# Central_Unit_V2.net
KiCad netlist of a schematic drawn in EAGLE
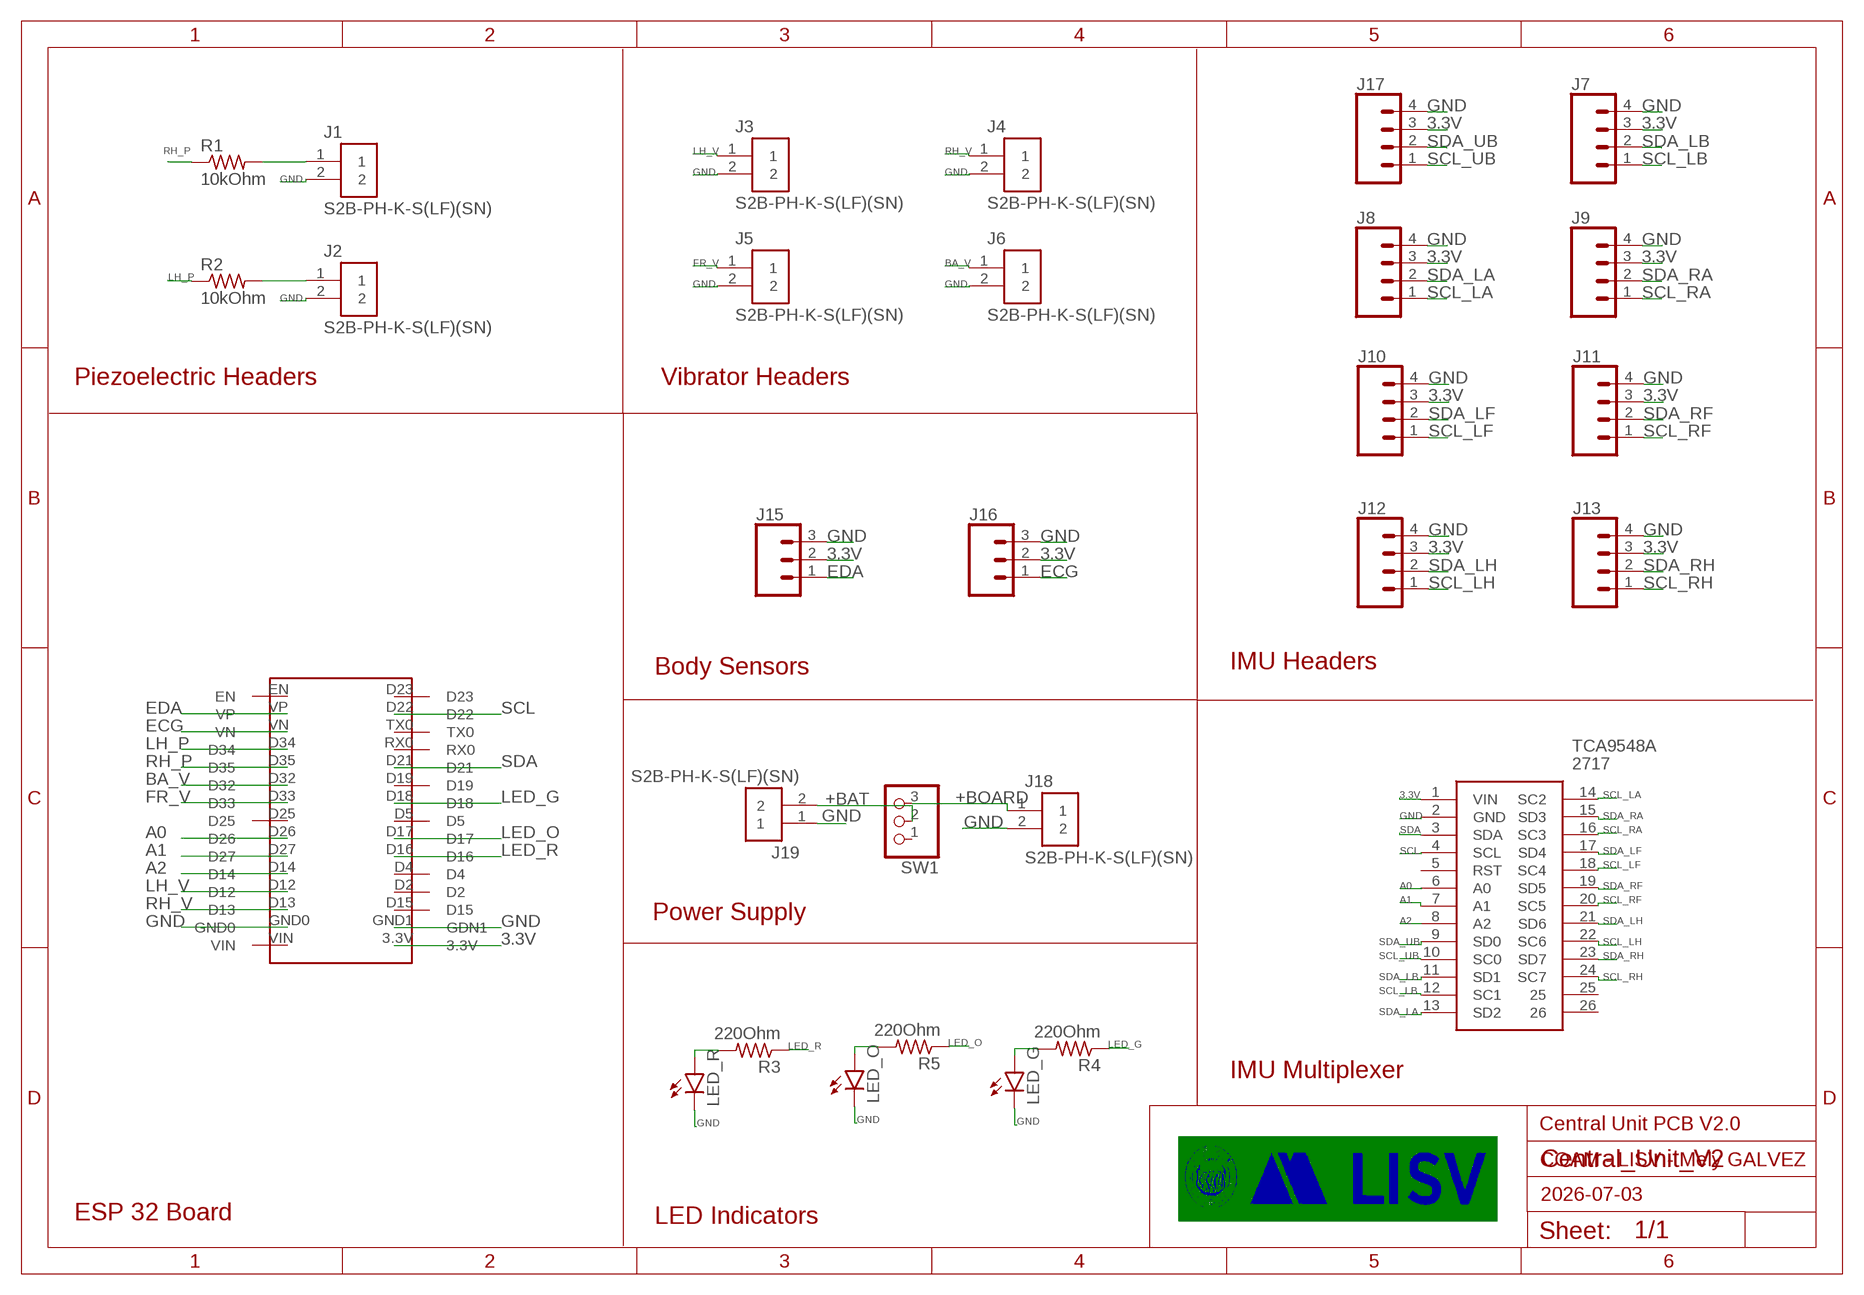
[diagram p0: schematic, sheet 1]

(export (version "E")
  (design (tool "Eeschema 10.0.6"))
  (components
    (comp (ref "J1")
      (value "S2B-PH-K-S(LF)(SN)")
      (footprint "eagle-import:S2B-PH-K-S(LF)(SN)")
      (fields
        (field (name "DIGI_KEY_PART_NUMBER") "455-1719-ND")
        (field (name "MANUFACTURER") "JST Sales America Inc.")
        (field (name "CREATED_BY") "PCBLayout.com")
      )
      (libsource (lib "eagle-import") (part "S2B-PH-K-S(LF)(SN)"))
    )
    (comp (ref "J2")
      (value "S2B-PH-K-S(LF)(SN)")
      (footprint "eagle-import:S2B-PH-K-S(LF)(SN)")
      (fields
        (field (name "DIGI_KEY_PART_NUMBER") "455-1719-ND")
        (field (name "MANUFACTURER") "JST Sales America Inc.")
        (field (name "CREATED_BY") "PCBLayout.com")
      )
      (libsource (lib "eagle-import") (part "S2B-PH-K-S(LF)(SN)"))
    )
    (comp (ref "J3")
      (value "S2B-PH-K-S(LF)(SN)")
      (footprint "eagle-import:S2B-PH-K-S(LF)(SN)")
      (fields
        (field (name "DIGI_KEY_PART_NUMBER") "455-1719-ND")
        (field (name "MANUFACTURER") "JST Sales America Inc.")
        (field (name "CREATED_BY") "PCBLayout.com")
      )
      (libsource (lib "eagle-import") (part "S2B-PH-K-S(LF)(SN)"))
    )
    (comp (ref "J4")
      (value "S2B-PH-K-S(LF)(SN)")
      (footprint "eagle-import:S2B-PH-K-S(LF)(SN)")
      (fields
        (field (name "DIGI_KEY_PART_NUMBER") "455-1719-ND")
        (field (name "MANUFACTURER") "JST Sales America Inc.")
        (field (name "CREATED_BY") "PCBLayout.com")
      )
      (libsource (lib "eagle-import") (part "S2B-PH-K-S(LF)(SN)"))
    )
    (comp (ref "J5")
      (value "S2B-PH-K-S(LF)(SN)")
      (footprint "eagle-import:S2B-PH-K-S(LF)(SN)")
      (fields
        (field (name "DIGI_KEY_PART_NUMBER") "455-1719-ND")
        (field (name "MANUFACTURER") "JST Sales America Inc.")
        (field (name "CREATED_BY") "PCBLayout.com")
      )
      (libsource (lib "eagle-import") (part "S2B-PH-K-S(LF)(SN)"))
    )
    (comp (ref "J6")
      (value "S2B-PH-K-S(LF)(SN)")
      (footprint "eagle-import:S2B-PH-K-S(LF)(SN)")
      (fields
        (field (name "DIGI_KEY_PART_NUMBER") "455-1719-ND")
        (field (name "MANUFACTURER") "JST Sales America Inc.")
        (field (name "CREATED_BY") "PCBLayout.com")
      )
      (libsource (lib "eagle-import") (part "S2B-PH-K-S(LF)(SN)"))
    )
    (comp (ref "J7")
      (value "CONN_04JST-PTH")
      (footprint "eagle-import:JST-4-PTH")
      (libsource (lib "eagle-import") (part "CONN_04JST-PTH"))
    )
    (comp (ref "J8")
      (value "CONN_04JST-PTH")
      (footprint "eagle-import:JST-4-PTH")
      (libsource (lib "eagle-import") (part "CONN_04JST-PTH"))
    )
    (comp (ref "J9")
      (value "CONN_04JST-PTH")
      (footprint "eagle-import:JST-4-PTH")
      (libsource (lib "eagle-import") (part "CONN_04JST-PTH"))
    )
    (comp (ref "J10")
      (value "CONN_04JST-PTH")
      (footprint "eagle-import:JST-4-PTH")
      (libsource (lib "eagle-import") (part "CONN_04JST-PTH"))
    )
    (comp (ref "J11")
      (value "CONN_04JST-PTH")
      (footprint "eagle-import:JST-4-PTH")
      (libsource (lib "eagle-import") (part "CONN_04JST-PTH"))
    )
    (comp (ref "J12")
      (value "CONN_04JST-PTH")
      (footprint "eagle-import:JST-4-PTH")
      (libsource (lib "eagle-import") (part "CONN_04JST-PTH"))
    )
    (comp (ref "J13")
      (value "CONN_04JST-PTH")
      (footprint "eagle-import:JST-4-PTH")
      (libsource (lib "eagle-import") (part "CONN_04JST-PTH"))
    )
    (comp (ref "J15")
      (value "CONN_03JST-PTH")
      (footprint "eagle-import:JST-3-PTH")
      (libsource (lib "eagle-import") (part "CONN_03JST-PTH"))
    )
    (comp (ref "J16")
      (value "CONN_03JST-PTH")
      (footprint "eagle-import:JST-3-PTH")
      (libsource (lib "eagle-import") (part "CONN_03JST-PTH"))
    )
    (comp (ref "J17")
      (value "CONN_04JST-PTH")
      (footprint "eagle-import:JST-4-PTH")
      (libsource (lib "eagle-import") (part "CONN_04JST-PTH"))
    )
    (comp (ref "J18")
      (value "S2B-PH-K-S(LF)(SN)")
      (footprint "eagle-import:S2B-PH-K-S(LF)(SN)")
      (fields
        (field (name "DIGI_KEY_PART_NUMBER") "455-1719-ND")
        (field (name "MANUFACTURER") "JST Sales America Inc.")
        (field (name "CREATED_BY") "PCBLayout.com")
      )
      (libsource (lib "eagle-import") (part "S2B-PH-K-S(LF)(SN)"))
    )
    (comp (ref "J19")
      (value "S2B-PH-K-S(LF)(SN)")
      (footprint "eagle-import:S2B-PH-K-S(LF)(SN)")
      (fields
        (field (name "DIGI_KEY_PART_NUMBER") "455-1719-ND")
        (field (name "MANUFACTURER") "JST Sales America Inc.")
        (field (name "CREATED_BY") "PCBLayout.com")
      )
      (libsource (lib "eagle-import") (part "S2B-PH-K-S(LF)(SN)"))
    )
    (comp (ref "LED_G")
      (value "LED3MM")
      (footprint "eagle-import:LED3MM")
      (libsource (lib "eagle-import") (part "LED3MM"))
    )
    (comp (ref "LED_O")
      (value "LED3MM")
      (footprint "eagle-import:LED3MM")
      (libsource (lib "eagle-import") (part "LED3MM"))
    )
    (comp (ref "LED_R")
      (value "LED3MM")
      (footprint "eagle-import:LED3MM")
      (libsource (lib "eagle-import") (part "LED3MM"))
    )
    (comp (ref "R1")
      (value "10kOhm")
      (footprint "eagle-import:0207_10")
      (libsource (lib "eagle-import") (part "R-US_0207/10"))
    )
    (comp (ref "R2")
      (value "10kOhm")
      (footprint "eagle-import:0207_10")
      (libsource (lib "eagle-import") (part "R-US_0207/10"))
    )
    (comp (ref "R3")
      (value "220Ohm")
      (footprint "eagle-import:0207_10")
      (libsource (lib "eagle-import") (part "R-US_0207/10"))
    )
    (comp (ref "R4")
      (value "220Ohm")
      (footprint "eagle-import:0207_10")
      (libsource (lib "eagle-import") (part "R-US_0207/10"))
    )
    (comp (ref "R5")
      (value "220Ohm")
      (footprint "eagle-import:0207_10")
      (libsource (lib "eagle-import") (part "R-US_0207/10"))
    )
    (comp (ref "SW1")
      (value "PINHD-1X3")
      (footprint "eagle-import:1X03")
      (libsource (lib "eagle-import") (part "PINHD-1X3"))
    )
    (comp (ref "TCA9548A")
      (value "2717")
      (footprint "eagle-import:2717")
      (fields (field (name "MOUSER_PART_NUMBER") "485-2717"))
      (libsource (lib "eagle-import") (part "2717"))
    )
    (comp (ref "U$1")
      (value "ESP32_WROUM32")
      (footprint "eagle-import:ESP32_WROUM32")
      (libsource (lib "eagle-import") (part "ESP32_WROUM32"))
    )
  )
  (nets
    (net (code "1") (name "/+BAT") (class "Default")
      (node (ref "J19") (pin "2") (pinfunction "2_2") (pintype "passive"))
      (node (ref "SW1") (pin "2") (pinfunction "2_2") (pintype "passive"))
    )
    (net (code "2") (name "/+BOARD") (class "Default")
      (node (ref "J18") (pin "1") (pinfunction "1_1") (pintype "passive"))
      (node (ref "SW1") (pin "3") (pinfunction "3_3") (pintype "passive"))
    )
    (net (code "3") (name "/3.3V") (class "Default")
      (node (ref "J10") (pin "3") (pinfunction "3_3") (pintype "passive"))
      (node (ref "J11") (pin "3") (pinfunction "3_3") (pintype "passive"))
      (node (ref "J12") (pin "3") (pinfunction "3_3") (pintype "passive"))
      (node (ref "J13") (pin "3") (pinfunction "3_3") (pintype "passive"))
      (node (ref "J15") (pin "2") (pinfunction "2_2") (pintype "passive"))
      (node (ref "J16") (pin "2") (pinfunction "2_2") (pintype "passive"))
      (node (ref "J17") (pin "3") (pinfunction "3_3") (pintype "passive"))
      (node (ref "J7") (pin "3") (pinfunction "3_3") (pintype "passive"))
      (node (ref "J8") (pin "3") (pinfunction "3_3") (pintype "passive"))
      (node (ref "J9") (pin "3") (pinfunction "3_3") (pintype "passive"))
      (node (ref "TCA9548A") (pin "1") (pinfunction "VIN_1") (pintype "bidirectional"))
      (node (ref "U$1") (pin "3.3V") (pinfunction "3.3V_3.3V") (pintype "output"))
    )
    (net (code "4") (name "/A0") (class "Default")
      (node (ref "TCA9548A") (pin "6") (pinfunction "A0_6") (pintype "bidirectional"))
      (node (ref "U$1") (pin "D26") (pinfunction "D26_D26") (pintype "bidirectional"))
    )
    (net (code "5") (name "/A1") (class "Default")
      (node (ref "TCA9548A") (pin "7") (pinfunction "A1_7") (pintype "bidirectional"))
      (node (ref "U$1") (pin "D27") (pinfunction "D27_D27") (pintype "bidirectional"))
    )
    (net (code "6") (name "/A2") (class "Default")
      (node (ref "TCA9548A") (pin "8") (pinfunction "A2_8") (pintype "bidirectional"))
      (node (ref "U$1") (pin "D14") (pinfunction "D14_D14") (pintype "bidirectional"))
    )
    (net (code "7") (name "/BA_V") (class "Default")
      (node (ref "J6") (pin "1") (pinfunction "1_1") (pintype "passive"))
      (node (ref "U$1") (pin "D32") (pinfunction "D32_D32") (pintype "bidirectional"))
    )
    (net (code "8") (name "/ECG") (class "Default")
      (node (ref "J16") (pin "1") (pinfunction "1_1") (pintype "passive"))
      (node (ref "U$1") (pin "VN") (pinfunction "VN_VN") (pintype "bidirectional"))
    )
    (net (code "9") (name "/EDA") (class "Default")
      (node (ref "J15") (pin "1") (pinfunction "1_1") (pintype "passive"))
      (node (ref "U$1") (pin "VP") (pinfunction "VP_VP") (pintype "bidirectional"))
    )
    (net (code "10") (name "/FR_V") (class "Default")
      (node (ref "J5") (pin "1") (pinfunction "1_1") (pintype "passive"))
      (node (ref "U$1") (pin "D33") (pinfunction "D33_D33") (pintype "bidirectional"))
    )
    (net (code "11") (name "/GND") (class "Default")
      (node (ref "J1") (pin "2") (pinfunction "2_2") (pintype "passive"))
      (node (ref "J10") (pin "4") (pinfunction "4_4") (pintype "passive"))
      (node (ref "J11") (pin "4") (pinfunction "4_4") (pintype "passive"))
      (node (ref "J12") (pin "4") (pinfunction "4_4") (pintype "passive"))
      (node (ref "J13") (pin "4") (pinfunction "4_4") (pintype "passive"))
      (node (ref "J15") (pin "3") (pinfunction "3_3") (pintype "passive"))
      (node (ref "J16") (pin "3") (pinfunction "3_3") (pintype "passive"))
      (node (ref "J17") (pin "4") (pinfunction "4_4") (pintype "passive"))
      (node (ref "J18") (pin "2") (pinfunction "2_2") (pintype "passive"))
      (node (ref "J19") (pin "1") (pinfunction "1_1") (pintype "passive"))
      (node (ref "J2") (pin "2") (pinfunction "2_2") (pintype "passive"))
      (node (ref "J3") (pin "2") (pinfunction "2_2") (pintype "passive"))
      (node (ref "J4") (pin "2") (pinfunction "2_2") (pintype "passive"))
      (node (ref "J5") (pin "2") (pinfunction "2_2") (pintype "passive"))
      (node (ref "J6") (pin "2") (pinfunction "2_2") (pintype "passive"))
      (node (ref "J7") (pin "4") (pinfunction "4_4") (pintype "passive"))
      (node (ref "J8") (pin "4") (pinfunction "4_4") (pintype "passive"))
      (node (ref "J9") (pin "4") (pinfunction "4_4") (pintype "passive"))
      (node (ref "LED_G") (pin "K") (pinfunction "C_K") (pintype "passive"))
      (node (ref "LED_O") (pin "K") (pinfunction "C_K") (pintype "passive"))
      (node (ref "LED_R") (pin "K") (pinfunction "C_K") (pintype "passive"))
      (node (ref "TCA9548A") (pin "2") (pinfunction "GND_2") (pintype "bidirectional"))
      (node (ref "U$1") (pin "GND0") (pinfunction "GND0_GND0") (pintype "output"))
      (node (ref "U$1") (pin "GND1") (pinfunction "GDN1_GND1") (pintype "output"))
    )
    (net (code "12") (name "/LED_G") (class "Default")
      (node (ref "R4") (pin "1") (pinfunction "1_1") (pintype "passive"))
      (node (ref "U$1") (pin "D18") (pinfunction "D18_D18") (pintype "bidirectional"))
    )
    (net (code "13") (name "/LED_O") (class "Default")
      (node (ref "R5") (pin "1") (pinfunction "1_1") (pintype "passive"))
      (node (ref "U$1") (pin "D17") (pinfunction "D17_D17") (pintype "bidirectional"))
    )
    (net (code "14") (name "/LED_R") (class "Default")
      (node (ref "R3") (pin "1") (pinfunction "1_1") (pintype "passive"))
      (node (ref "U$1") (pin "D16") (pinfunction "D16_D16") (pintype "bidirectional"))
    )
    (net (code "15") (name "/LH_P") (class "Default")
      (node (ref "R2") (pin "1") (pinfunction "1_1") (pintype "passive"))
      (node (ref "U$1") (pin "D34") (pinfunction "D34_D34") (pintype "bidirectional"))
    )
    (net (code "16") (name "/LH_V") (class "Default")
      (node (ref "J3") (pin "1") (pinfunction "1_1") (pintype "passive"))
      (node (ref "U$1") (pin "D12") (pinfunction "D12_D12") (pintype "bidirectional"))
    )
    (net (code "17") (name "/RH_P") (class "Default")
      (node (ref "R1") (pin "1") (pinfunction "1_1") (pintype "passive"))
      (node (ref "U$1") (pin "D35") (pinfunction "D35_D35") (pintype "bidirectional"))
    )
    (net (code "18") (name "/RH_V") (class "Default")
      (node (ref "J4") (pin "1") (pinfunction "1_1") (pintype "passive"))
      (node (ref "U$1") (pin "D13") (pinfunction "D13_D13") (pintype "bidirectional"))
    )
    (net (code "19") (name "/SCL") (class "Default")
      (node (ref "TCA9548A") (pin "4") (pinfunction "SCL_4") (pintype "bidirectional"))
      (node (ref "U$1") (pin "D22") (pinfunction "D22_D22") (pintype "bidirectional"))
    )
    (net (code "20") (name "/SCL_LA") (class "Default")
      (node (ref "J8") (pin "1") (pinfunction "1_1") (pintype "passive"))
      (node (ref "TCA9548A") (pin "14") (pinfunction "SC2_14") (pintype "bidirectional"))
    )
    (net (code "21") (name "/SCL_LB") (class "Default")
      (node (ref "J7") (pin "1") (pinfunction "1_1") (pintype "passive"))
      (node (ref "TCA9548A") (pin "12") (pinfunction "SC1_12") (pintype "bidirectional"))
    )
    (net (code "22") (name "/SCL_LF") (class "Default")
      (node (ref "J10") (pin "1") (pinfunction "1_1") (pintype "passive"))
      (node (ref "TCA9548A") (pin "18") (pinfunction "SC4_18") (pintype "bidirectional"))
    )
    (net (code "23") (name "/SCL_LH") (class "Default")
      (node (ref "J12") (pin "1") (pinfunction "1_1") (pintype "passive"))
      (node (ref "TCA9548A") (pin "22") (pinfunction "SC6_22") (pintype "bidirectional"))
    )
    (net (code "24") (name "/SCL_RA") (class "Default")
      (node (ref "J9") (pin "1") (pinfunction "1_1") (pintype "passive"))
      (node (ref "TCA9548A") (pin "16") (pinfunction "SC3_16") (pintype "bidirectional"))
    )
    (net (code "25") (name "/SCL_RF") (class "Default")
      (node (ref "J11") (pin "1") (pinfunction "1_1") (pintype "passive"))
      (node (ref "TCA9548A") (pin "20") (pinfunction "SC5_20") (pintype "bidirectional"))
    )
    (net (code "26") (name "/SCL_RH") (class "Default")
      (node (ref "J13") (pin "1") (pinfunction "1_1") (pintype "passive"))
      (node (ref "TCA9548A") (pin "24") (pinfunction "SC7_24") (pintype "bidirectional"))
    )
    (net (code "27") (name "/SCL_UB") (class "Default")
      (node (ref "J17") (pin "1") (pinfunction "1_1") (pintype "passive"))
      (node (ref "TCA9548A") (pin "10") (pinfunction "SC0_10") (pintype "bidirectional"))
    )
    (net (code "28") (name "/SDA") (class "Default")
      (node (ref "TCA9548A") (pin "3") (pinfunction "SDA_3") (pintype "bidirectional"))
      (node (ref "U$1") (pin "D21") (pinfunction "D21_D21") (pintype "bidirectional"))
    )
    (net (code "29") (name "/SDA_LA") (class "Default")
      (node (ref "J8") (pin "2") (pinfunction "2_2") (pintype "passive"))
      (node (ref "TCA9548A") (pin "13") (pinfunction "SD2_13") (pintype "bidirectional"))
    )
    (net (code "30") (name "/SDA_LB") (class "Default")
      (node (ref "J7") (pin "2") (pinfunction "2_2") (pintype "passive"))
      (node (ref "TCA9548A") (pin "11") (pinfunction "SD1_11") (pintype "bidirectional"))
    )
    (net (code "31") (name "/SDA_LF") (class "Default")
      (node (ref "J10") (pin "2") (pinfunction "2_2") (pintype "passive"))
      (node (ref "TCA9548A") (pin "17") (pinfunction "SD4_17") (pintype "bidirectional"))
    )
    (net (code "32") (name "/SDA_LH") (class "Default")
      (node (ref "J12") (pin "2") (pinfunction "2_2") (pintype "passive"))
      (node (ref "TCA9548A") (pin "21") (pinfunction "SD6_21") (pintype "bidirectional"))
    )
    (net (code "33") (name "/SDA_RA") (class "Default")
      (node (ref "J9") (pin "2") (pinfunction "2_2") (pintype "passive"))
      (node (ref "TCA9548A") (pin "15") (pinfunction "SD3_15") (pintype "bidirectional"))
    )
    (net (code "34") (name "/SDA_RF") (class "Default")
      (node (ref "J11") (pin "2") (pinfunction "2_2") (pintype "passive"))
      (node (ref "TCA9548A") (pin "19") (pinfunction "SD5_19") (pintype "bidirectional"))
    )
    (net (code "35") (name "/SDA_RH") (class "Default")
      (node (ref "J13") (pin "2") (pinfunction "2_2") (pintype "passive"))
      (node (ref "TCA9548A") (pin "23") (pinfunction "SD7_23") (pintype "bidirectional"))
    )
    (net (code "36") (name "/SDA_UB") (class "Default")
      (node (ref "J17") (pin "2") (pinfunction "2_2") (pintype "passive"))
      (node (ref "TCA9548A") (pin "9") (pinfunction "SD0_9") (pintype "bidirectional"))
    )
    (net (code "37") (name "Net-(J1-Pad1)") (class "Default")
      (node (ref "J1") (pin "1") (pinfunction "1_1") (pintype "passive"))
      (node (ref "R1") (pin "2") (pinfunction "2_2") (pintype "passive"))
    )
    (net (code "38") (name "Net-(J2-Pad1)") (class "Default")
      (node (ref "J2") (pin "1") (pinfunction "1_1") (pintype "passive"))
      (node (ref "R2") (pin "2") (pinfunction "2_2") (pintype "passive"))
    )
    (net (code "39") (name "Net-(LED_G-PadA)") (class "Default")
      (node (ref "LED_G") (pin "A") (pinfunction "A_A") (pintype "passive"))
      (node (ref "R4") (pin "2") (pinfunction "2_2") (pintype "passive"))
    )
    (net (code "40") (name "Net-(LED_O-PadA)") (class "Default")
      (node (ref "LED_O") (pin "A") (pinfunction "A_A") (pintype "passive"))
      (node (ref "R5") (pin "2") (pinfunction "2_2") (pintype "passive"))
    )
    (net (code "41") (name "Net-(LED_R-PadA)") (class "Default")
      (node (ref "LED_R") (pin "A") (pinfunction "A_A") (pintype "passive"))
      (node (ref "R3") (pin "2") (pinfunction "2_2") (pintype "passive"))
    )
    (net (code "42") (name "unconnected-(SW1-Pad1)") (class "Default")
      (node (ref "SW1") (pin "1") (pinfunction "1_1") (pintype "passive"))
    )
    (net (code "43") (name "unconnected-(TCA9548A-Pad25)") (class "Default")
      (node (ref "TCA9548A") (pin "25") (pinfunction "25_25") (pintype "bidirectional"))
    )
    (net (code "44") (name "unconnected-(TCA9548A-Pad26)") (class "Default")
      (node (ref "TCA9548A") (pin "26") (pinfunction "26_26") (pintype "bidirectional"))
    )
    (net (code "45") (name "unconnected-(TCA9548A-RST-Pad5)") (class "Default")
      (node (ref "TCA9548A") (pin "5") (pinfunction "RST_5") (pintype "bidirectional"))
    )
    (net (code "46") (name "unconnected-(U$1-PadD2)") (class "Default")
      (node (ref "U$1") (pin "D2") (pinfunction "D2_D2") (pintype "bidirectional"))
    )
    (net (code "47") (name "unconnected-(U$1-PadD4)") (class "Default")
      (node (ref "U$1") (pin "D4") (pinfunction "D4_D4") (pintype "bidirectional"))
    )
    (net (code "48") (name "unconnected-(U$1-PadD5)") (class "Default")
      (node (ref "U$1") (pin "D5") (pinfunction "D5_D5") (pintype "bidirectional"))
    )
    (net (code "49") (name "unconnected-(U$1-PadD15)") (class "Default")
      (node (ref "U$1") (pin "D15") (pinfunction "D15_D15") (pintype "bidirectional"))
    )
    (net (code "50") (name "unconnected-(U$1-PadD19)") (class "Default")
      (node (ref "U$1") (pin "D19") (pinfunction "D19_D19") (pintype "bidirectional"))
    )
    (net (code "51") (name "unconnected-(U$1-PadD23)") (class "Default")
      (node (ref "U$1") (pin "D23") (pinfunction "D23_D23") (pintype "bidirectional"))
    )
    (net (code "52") (name "unconnected-(U$1-PadD25)") (class "Default")
      (node (ref "U$1") (pin "D25") (pinfunction "D25_D25") (pintype "bidirectional"))
    )
    (net (code "53") (name "unconnected-(U$1-PadEN)") (class "Default")
      (node (ref "U$1") (pin "EN") (pinfunction "EN_EN") (pintype "bidirectional"))
    )
    (net (code "54") (name "unconnected-(U$1-PadRX0)") (class "Default")
      (node (ref "U$1") (pin "RX0") (pinfunction "RX0_RX0") (pintype "bidirectional"))
    )
    (net (code "55") (name "unconnected-(U$1-PadTX0)") (class "Default")
      (node (ref "U$1") (pin "TX0") (pinfunction "TX0_TX0") (pintype "bidirectional"))
    )
    (net (code "56") (name "unconnected-(U$1-PadVIN)") (class "Default")
      (node (ref "U$1") (pin "VIN") (pinfunction "VIN_VIN") (pintype "output"))
    )
  )
)
